# hk310_esc.net
KiCad netlist of a schematic drawn in EAGLE
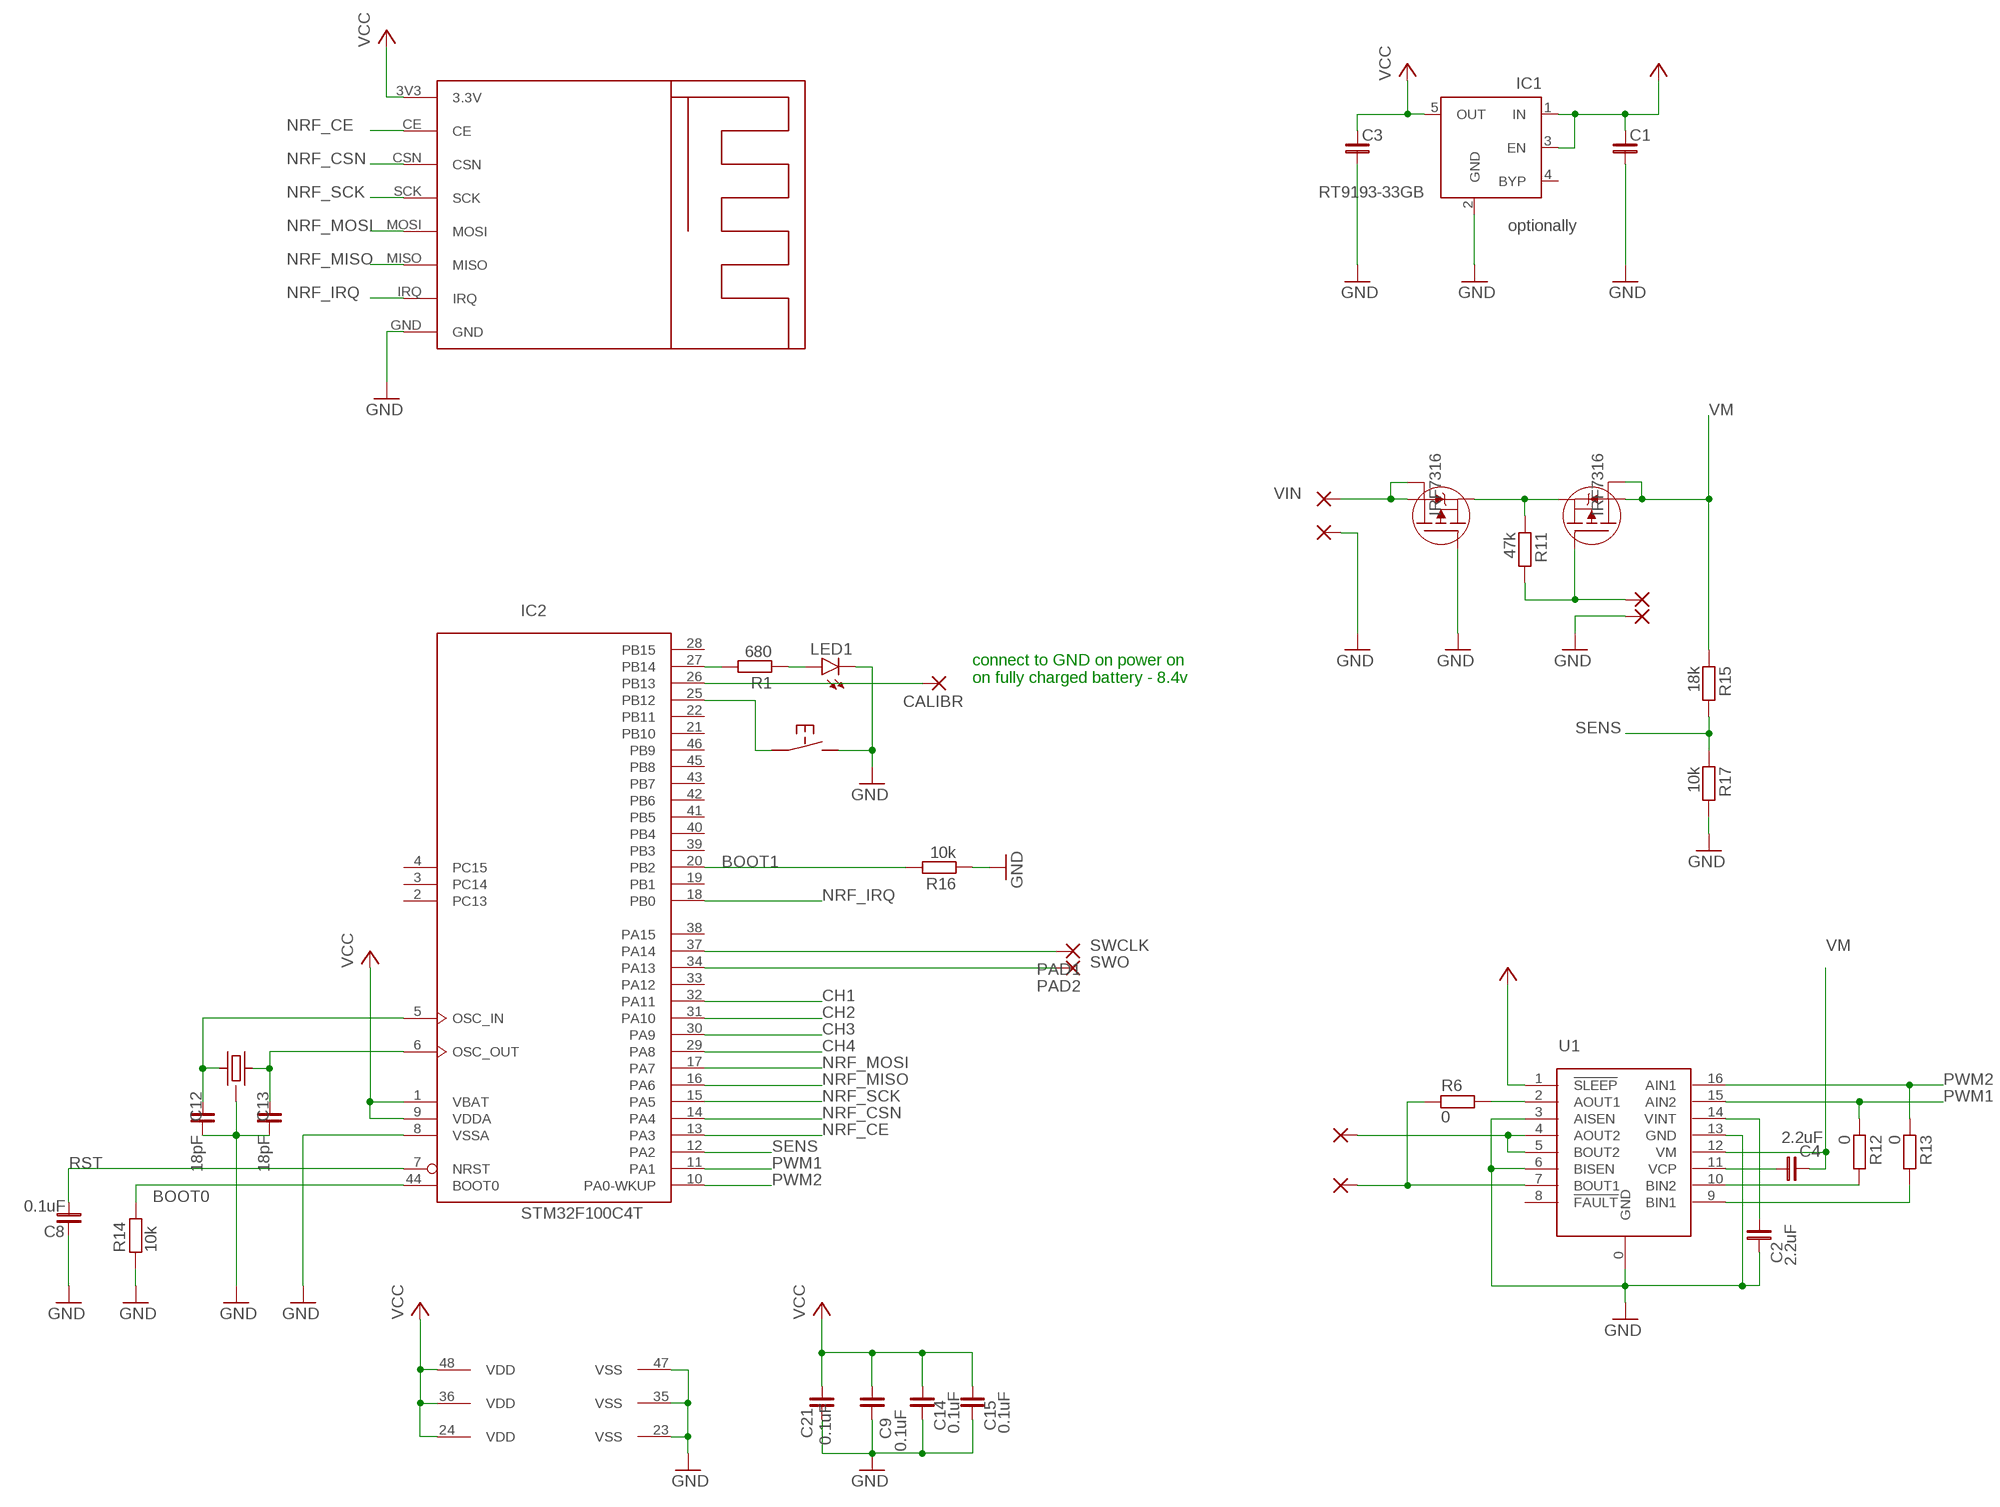
[diagram p0: schematic, sheet 1, part 1 of 2]
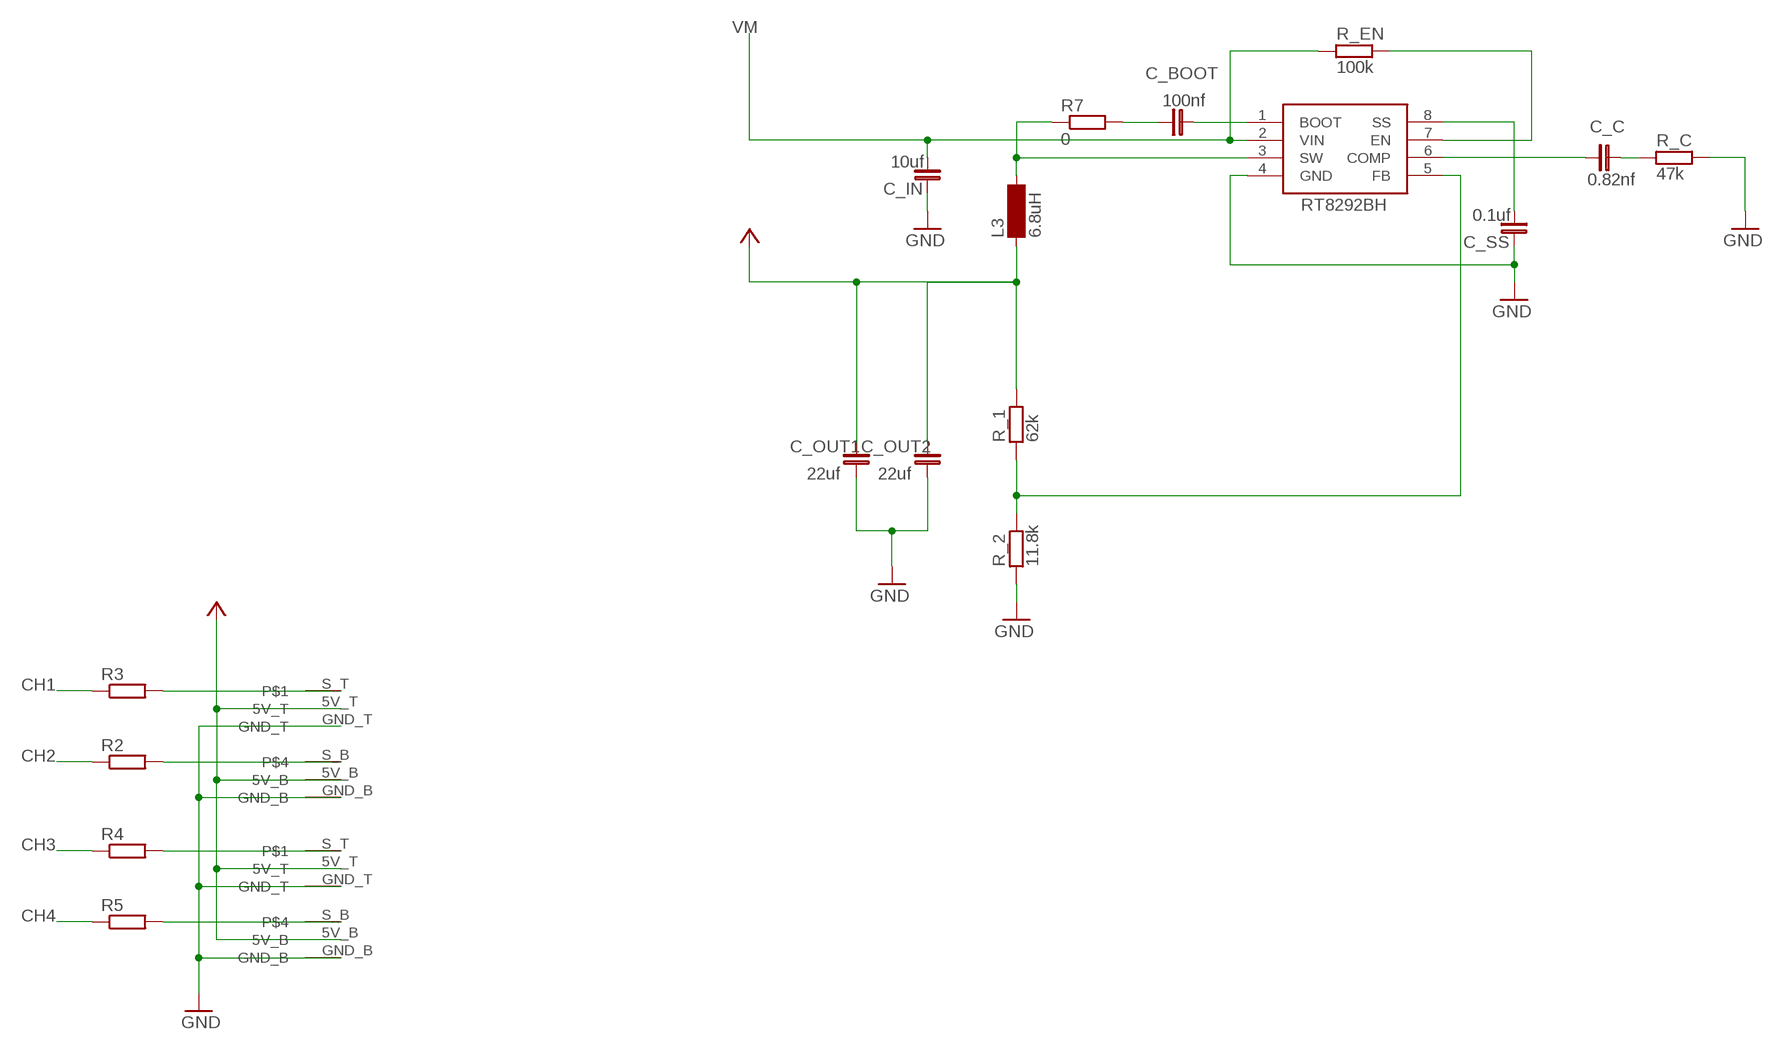
[diagram p1: schematic, sheet 1, part 2 of 2]

(export (version "E")
  (design (tool "Eeschema 10.0.6"))
  (components
    (comp (ref "C1")
      (value "C_0805")
      (footprint "eagle-import:C0805")
      (libsource (lib "eagle-import") (part "C_0805"))
    )
    (comp (ref "C2")
      (value "2.2uF")
      (footprint "eagle-import:C0805")
      (libsource (lib "eagle-import") (part "C_0805"))
    )
    (comp (ref "C3")
      (value "C_0805")
      (footprint "eagle-import:C0805")
      (libsource (lib "eagle-import") (part "C_0805"))
    )
    (comp (ref "C4")
      (value "2.2uF")
      (footprint "eagle-import:C0805")
      (libsource (lib "eagle-import") (part "C_0805"))
    )
    (comp (ref "C8")
      (value "0.1uF")
      (footprint "eagle-import:C0603")
      (libsource (lib "eagle-import") (part "C_0603"))
    )
    (comp (ref "C9")
      (value "0.1uF")
      (footprint "eagle-import:C0603")
      (libsource (lib "eagle-import") (part "C_0603"))
    )
    (comp (ref "C12")
      (value "18pF")
      (footprint "eagle-import:C0603")
      (libsource (lib "eagle-import") (part "C_0603"))
    )
    (comp (ref "C13")
      (value "18pF")
      (footprint "eagle-import:C0603")
      (libsource (lib "eagle-import") (part "C_0603"))
    )
    (comp (ref "C14")
      (value "0.1uF")
      (footprint "eagle-import:C0603")
      (libsource (lib "eagle-import") (part "C_0603"))
    )
    (comp (ref "C15")
      (value "0.1uF")
      (footprint "eagle-import:C0603")
      (libsource (lib "eagle-import") (part "C_0603"))
    )
    (comp (ref "C21")
      (value "0.1uF")
      (footprint "eagle-import:C0603")
      (libsource (lib "eagle-import") (part "C_0603"))
    )
    (comp (ref "CALIBR")
      (value "SMD2")
      (footprint "eagle-import:SMD1,27-2,54")
      (libsource (lib "eagle-import") (part "SMD2"))
    )
    (comp (ref "C_BOOT")
      (value "100nf")
      (footprint "eagle-import:C0402")
      (libsource (lib "eagle-import") (part "C_0402"))
    )
    (comp (ref "C_C")
      (value "0.82nf")
      (footprint "eagle-import:C0402")
      (libsource (lib "eagle-import") (part "C_0402"))
    )
    (comp (ref "C_IN")
      (value "10uf")
      (footprint "eagle-import:C1206")
      (libsource (lib "eagle-import") (part "C_1206"))
    )
    (comp (ref "C_OUT1")
      (value "22uf")
      (footprint "eagle-import:C0805")
      (libsource (lib "eagle-import") (part "C_0805"))
    )
    (comp (ref "C_OUT2")
      (value "22uf")
      (footprint "eagle-import:C0805")
      (libsource (lib "eagle-import") (part "C_0805"))
    )
    (comp (ref "C_SS")
      (value "0.1uf")
      (footprint "eagle-import:C0402")
      (libsource (lib "eagle-import") (part "C_0402"))
    )
    (comp (ref "IC1")
      (value "RT9193-33GB")
      (footprint "eagle-import:SOT23-5")
      (libsource (lib "eagle-import") (part "MIC5219XX"))
    )
    (comp (ref "IC2")
      (value "STM32F100C4T")
      (footprint "eagle-import:LQFP48")
      (libsource (lib "eagle-import") (part "STM32F100CT4"))
    )
    (comp (ref "L3")
      (value "6.8uH")
      (footprint "eagle-import:MS85")
      (libsource (lib "eagle-import") (part "MS85"))
    )
    (comp (ref "LED1")
      (value "LED")
      (footprint "eagle-import:SMARTLED-TTW")
      (libsource (lib "eagle-import") (part "LED"))
    )
    (comp (ref "PAD1")
      (value "SMD2")
      (footprint "eagle-import:SMD1,27-2,54")
      (libsource (lib "eagle-import") (part "SMD2"))
    )
    (comp (ref "PAD2")
      (value "SMD2")
      (footprint "eagle-import:SMD1,27-2,54")
      (libsource (lib "eagle-import") (part "SMD2"))
    )
    (comp (ref "PAD3")
      (value "WIREPADSMD5-1,8")
      (footprint "eagle-import:5-1,8")
      (libsource (lib "eagle-import") (part "WIREPADSMD5-1,8"))
    )
    (comp (ref "PAD4")
      (value "WIREPADSMD5-1,8")
      (footprint "eagle-import:5-1,8")
      (libsource (lib "eagle-import") (part "WIREPADSMD5-1,8"))
    )
    (comp (ref "PAD5")
      (value "WIREPADSMD5-1,8")
      (footprint "eagle-import:5-1,8")
      (libsource (lib "eagle-import") (part "WIREPADSMD5-1,8"))
    )
    (comp (ref "PAD6")
      (value "WIREPADSMD5-1,8")
      (footprint "eagle-import:5-1,8")
      (libsource (lib "eagle-import") (part "WIREPADSMD5-1,8"))
    )
    (comp (ref "PAD7")
      (value "WIREPADSMD5-1,8")
      (footprint "eagle-import:5-1,8")
      (libsource (lib "eagle-import") (part "WIREPADSMD5-1,8"))
    )
    (comp (ref "PAD8")
      (value "WIREPADSMD5-1,8")
      (footprint "eagle-import:5-1,8")
      (libsource (lib "eagle-import") (part "WIREPADSMD5-1,8"))
    )
    (comp (ref "R1")
      (value "680")
      (footprint "eagle-import:R0805")
      (libsource (lib "eagle-import") (part "R_0805"))
    )
    (comp (ref "R2")
      (value "R-EU_R1206")
      (footprint "eagle-import:R1206")
      (libsource (lib "eagle-import") (part "R-EU_R1206"))
    )
    (comp (ref "R3")
      (value "R-EU_R1206")
      (footprint "eagle-import:R1206")
      (libsource (lib "eagle-import") (part "R-EU_R1206"))
    )
    (comp (ref "R4")
      (value "R-EU_R1206")
      (footprint "eagle-import:R1206")
      (libsource (lib "eagle-import") (part "R-EU_R1206"))
    )
    (comp (ref "R5")
      (value "R-EU_R1206")
      (footprint "eagle-import:R1206")
      (libsource (lib "eagle-import") (part "R-EU_R1206"))
    )
    (comp (ref "R6")
      (value "0")
      (footprint "eagle-import:R1206")
      (libsource (lib "eagle-import") (part "R_1206"))
    )
    (comp (ref "R7")
      (value "0")
      (footprint "eagle-import:R1206")
      (libsource (lib "eagle-import") (part "R-EU_R1206"))
    )
    (comp (ref "R11")
      (value "47k")
      (footprint "eagle-import:R0805")
      (libsource (lib "eagle-import") (part "R_0805"))
    )
    (comp (ref "R12")
      (value "0")
      (footprint "eagle-import:R1206")
      (libsource (lib "eagle-import") (part "R_1206"))
    )
    (comp (ref "R13")
      (value "0")
      (footprint "eagle-import:R1206")
      (libsource (lib "eagle-import") (part "R_1206"))
    )
    (comp (ref "R14")
      (value "10k")
      (footprint "eagle-import:R0805")
      (libsource (lib "eagle-import") (part "R_0805"))
    )
    (comp (ref "R15")
      (value "18k")
      (footprint "eagle-import:R0805")
      (libsource (lib "eagle-import") (part "R_0805"))
    )
    (comp (ref "R16")
      (value "10k")
      (footprint "eagle-import:R0805")
      (libsource (lib "eagle-import") (part "R_0805"))
    )
    (comp (ref "R17")
      (value "10k")
      (footprint "eagle-import:R0805")
      (libsource (lib "eagle-import") (part "R_0805"))
    )
    (comp (ref "RT8292BH")
      (value "RT8292B")
      (footprint "eagle-import:SO8-2")
      (libsource (lib "eagle-import") (part "RT8292B"))
    )
    (comp (ref "R_1")
      (value "62k")
      (footprint "eagle-import:R0402")
      (libsource (lib "eagle-import") (part "R_0402"))
    )
    (comp (ref "R_2")
      (value "11.8k")
      (footprint "eagle-import:R0402")
      (libsource (lib "eagle-import") (part "R_0402"))
    )
    (comp (ref "R_C")
      (value "47k")
      (footprint "eagle-import:R0402")
      (libsource (lib "eagle-import") (part "R_0402"))
    )
    (comp (ref "R_EN")
      (value "100k")
      (footprint "eagle-import:R0402")
      (libsource (lib "eagle-import") (part "R_0402"))
    )
    (comp (ref "U$1")
      (value "NRF24MINI")
      (footprint "eagle-import:NRF24MINI")
      (libsource (lib "eagle-import") (part "NRF24MINI"))
    )
    (comp (ref "U$2")
      (value "PINHEAD_SMD")
      (footprint "eagle-import:PINHEAD_SMD")
      (libsource (lib "eagle-import") (part "PINHEAD_SMD"))
    )
    (comp (ref "U$3")
      (value "PINHEAD_SMD")
      (footprint "eagle-import:PINHEAD_SMD")
      (libsource (lib "eagle-import") (part "PINHEAD_SMD"))
    )
    (comp (ref "U$5")
      (value "IRF7104")
      (footprint "eagle-import:SO8-2")
      (libsource (lib "eagle-import") (part "IRF7104"))
    )
    (comp (ref "U$6")
      (value "8Mhz")
      (footprint "eagle-import:CRYSTAL_3PINS")
      (libsource (lib "eagle-import") (part "CRYSTAL_3PINS"))
    )
    (comp (ref "U$7")
      (value "SMALL_BUTTON")
      (footprint "eagle-import:SMALL_BUTTON")
      (libsource (lib "eagle-import") (part "SMALL_BUTTON"))
    )
    (comp (ref "U1")
      (value "DRV8833")
      (footprint "eagle-import:PWP16")
      (libsource (lib "eagle-import") (part "DRV8833"))
    )
  )
  (nets
    (net (code "1") (name "+5V") (class "Default")
      (node (ref "C1") (pin "1") (pinfunction "1_1") (pintype "passive"))
      (node (ref "C_OUT1") (pin "2") (pinfunction "2_2") (pintype "passive"))
      (node (ref "C_OUT2") (pin "2") (pinfunction "2_2") (pintype "passive"))
      (node (ref "IC1") (pin "1") (pinfunction "IN_1") (pintype "input"))
      (node (ref "IC1") (pin "3") (pinfunction "EN_3") (pintype "input"))
      (node (ref "L3") (pin "1") (pinfunction "1_1") (pintype "passive"))
      (node (ref "R_1") (pin "2") (pinfunction "2_2") (pintype "passive"))
      (node (ref "U$2") (pin "5V_B") (pinfunction "5V_B_5V_B") (pintype "bidirectional"))
      (node (ref "U$2") (pin "5V_T") (pinfunction "5V_T_5V_T") (pintype "bidirectional"))
      (node (ref "U$3") (pin "5V_B") (pinfunction "5V_B_5V_B") (pintype "bidirectional"))
      (node (ref "U$3") (pin "5V_T") (pinfunction "5V_T_5V_T") (pintype "bidirectional"))
      (node (ref "U1") (pin "1") (pinfunction "~{SLEEP}_1") (pintype "bidirectional"))
    )
    (net (code "2") (name "/BOOT0") (class "Default")
      (node (ref "IC2") (pin "44") (pinfunction "BOOT0_44") (pintype "input"))
      (node (ref "R14") (pin "2") (pinfunction "2_2") (pintype "passive"))
    )
    (net (code "3") (name "/BOOT1") (class "Default")
      (node (ref "IC2") (pin "20") (pinfunction "PB2_20") (pintype "bidirectional"))
      (node (ref "R16") (pin "2") (pinfunction "2_2") (pintype "passive"))
    )
    (net (code "4") (name "/CH1") (class "Default")
      (node (ref "IC2") (pin "32") (pinfunction "PA11_32") (pintype "bidirectional"))
      (node (ref "R3") (pin "1") (pinfunction "1_1") (pintype "passive"))
    )
    (net (code "5") (name "/CH2") (class "Default")
      (node (ref "IC2") (pin "31") (pinfunction "PA10_31") (pintype "bidirectional"))
      (node (ref "R2") (pin "1") (pinfunction "1_1") (pintype "passive"))
    )
    (net (code "6") (name "/CH3") (class "Default")
      (node (ref "IC2") (pin "30") (pinfunction "PA9_30") (pintype "bidirectional"))
      (node (ref "R4") (pin "1") (pinfunction "1_1") (pintype "passive"))
    )
    (net (code "7") (name "/CH4") (class "Default")
      (node (ref "IC2") (pin "29") (pinfunction "PA8_29") (pintype "bidirectional"))
      (node (ref "R5") (pin "1") (pinfunction "1_1") (pintype "passive"))
    )
    (net (code "8") (name "/NRF_CE") (class "Default")
      (node (ref "IC2") (pin "13") (pinfunction "PA3_13") (pintype "bidirectional"))
      (node (ref "U$1") (pin "CE") (pinfunction "CE_CE") (pintype "bidirectional"))
    )
    (net (code "9") (name "/NRF_CSN") (class "Default")
      (node (ref "IC2") (pin "14") (pinfunction "PA4_14") (pintype "bidirectional"))
      (node (ref "U$1") (pin "CSN") (pinfunction "CSN_CSN") (pintype "bidirectional"))
    )
    (net (code "10") (name "/NRF_IRQ") (class "Default")
      (node (ref "IC2") (pin "18") (pinfunction "PB0_18") (pintype "bidirectional"))
      (node (ref "U$1") (pin "IRQ") (pinfunction "IRQ_IRQ") (pintype "bidirectional"))
    )
    (net (code "11") (name "/NRF_MISO") (class "Default")
      (node (ref "IC2") (pin "16") (pinfunction "PA6_16") (pintype "bidirectional"))
      (node (ref "U$1") (pin "MISO") (pinfunction "MISO_MISO") (pintype "bidirectional"))
    )
    (net (code "12") (name "/NRF_MOSI") (class "Default")
      (node (ref "IC2") (pin "17") (pinfunction "PA7_17") (pintype "bidirectional"))
      (node (ref "U$1") (pin "MOSI") (pinfunction "MOSI_MOSI") (pintype "bidirectional"))
    )
    (net (code "13") (name "/NRF_SCK") (class "Default")
      (node (ref "IC2") (pin "15") (pinfunction "PA5_15") (pintype "bidirectional"))
      (node (ref "U$1") (pin "SCK") (pinfunction "SCK_SCK") (pintype "bidirectional"))
    )
    (net (code "14") (name "/PWM1") (class "Default")
      (node (ref "IC2") (pin "11") (pinfunction "PA1_11") (pintype "bidirectional"))
      (node (ref "R12") (pin "1") (pinfunction "1_1") (pintype "passive"))
      (node (ref "U1") (pin "15") (pinfunction "AIN2_15") (pintype "bidirectional"))
    )
    (net (code "15") (name "/PWM2") (class "Default")
      (node (ref "IC2") (pin "10") (pinfunction "PA0-WKUP_10") (pintype "bidirectional"))
      (node (ref "R13") (pin "1") (pinfunction "1_1") (pintype "passive"))
      (node (ref "U1") (pin "16") (pinfunction "AIN1_16") (pintype "bidirectional"))
    )
    (net (code "16") (name "/RST") (class "Default")
      (node (ref "C8") (pin "2") (pinfunction "2_2") (pintype "passive"))
      (node (ref "IC2") (pin "7") (pinfunction "NRST_7") (pintype "bidirectional"))
    )
    (net (code "17") (name "/SENS") (class "Default")
      (node (ref "IC2") (pin "12") (pinfunction "PA2_12") (pintype "bidirectional"))
      (node (ref "R15") (pin "2") (pinfunction "2_2") (pintype "passive"))
      (node (ref "R17") (pin "1") (pinfunction "1_1") (pintype "passive"))
    )
    (net (code "18") (name "/SWCLK") (class "Default")
      (node (ref "IC2") (pin "37") (pinfunction "PA14_37") (pintype "bidirectional"))
      (node (ref "PAD1") (pin "1") (pinfunction "P_1") (pintype "passive"))
    )
    (net (code "19") (name "/SWO") (class "Default")
      (node (ref "IC2") (pin "34") (pinfunction "PA13_34") (pintype "bidirectional"))
      (node (ref "PAD2") (pin "1") (pinfunction "P_1") (pintype "passive"))
    )
    (net (code "20") (name "/VIN") (class "Default")
      (node (ref "PAD4") (pin "1") (pinfunction "P_1") (pintype "passive"))
      (node (ref "U$5") (pin "5") (pinfunction "D_5") (pintype "bidirectional"))
      (node (ref "U$5") (pin "6") (pinfunction "D_6") (pintype "bidirectional"))
    )
    (net (code "21") (name "/VM") (class "Default")
      (node (ref "C4") (pin "1") (pinfunction "1_1") (pintype "passive"))
      (node (ref "C_IN") (pin "2") (pinfunction "2_2") (pintype "passive"))
      (node (ref "R15") (pin "1") (pinfunction "1_1") (pintype "passive"))
      (node (ref "RT8292BH") (pin "2") (pinfunction "VIN_2") (pintype "bidirectional"))
      (node (ref "R_EN") (pin "1") (pinfunction "1_1") (pintype "passive"))
      (node (ref "U$5") (pin "7") (pinfunction "D_7") (pintype "bidirectional"))
      (node (ref "U$5") (pin "8") (pinfunction "D_8") (pintype "bidirectional"))
      (node (ref "U1") (pin "12") (pinfunction "VM_12") (pintype "bidirectional"))
    )
    (net (code "22") (name "GND") (class "Default")
      (node (ref "C1") (pin "2") (pinfunction "2_2") (pintype "passive"))
      (node (ref "C12") (pin "1") (pinfunction "1_1") (pintype "passive"))
      (node (ref "C13") (pin "1") (pinfunction "1_1") (pintype "passive"))
      (node (ref "C14") (pin "1") (pinfunction "1_1") (pintype "passive"))
      (node (ref "C15") (pin "1") (pinfunction "1_1") (pintype "passive"))
      (node (ref "C2") (pin "1") (pinfunction "1_1") (pintype "passive"))
      (node (ref "C21") (pin "1") (pinfunction "1_1") (pintype "passive"))
      (node (ref "C3") (pin "2") (pinfunction "2_2") (pintype "passive"))
      (node (ref "C8") (pin "1") (pinfunction "1_1") (pintype "passive"))
      (node (ref "C9") (pin "1") (pinfunction "1_1") (pintype "passive"))
      (node (ref "C_IN") (pin "1") (pinfunction "1_1") (pintype "passive"))
      (node (ref "C_OUT1") (pin "1") (pinfunction "1_1") (pintype "passive"))
      (node (ref "C_OUT2") (pin "1") (pinfunction "1_1") (pintype "passive"))
      (node (ref "C_SS") (pin "1") (pinfunction "1_1") (pintype "passive"))
      (node (ref "IC1") (pin "2") (pinfunction "GND_2") (pintype "power_in"))
      (node (ref "IC2") (pin "23") (pinfunction "VSS_23") (pintype "power_in"))
      (node (ref "IC2") (pin "35") (pinfunction "VSS_35") (pintype "power_in"))
      (node (ref "IC2") (pin "47") (pinfunction "VSS_47") (pintype "power_in"))
      (node (ref "IC2") (pin "8") (pinfunction "VSSA_8") (pintype "power_in"))
      (node (ref "LED1") (pin "C@1") (pinfunction "C_C@1") (pintype "passive"))
      (node (ref "PAD5") (pin "1") (pinfunction "P_1") (pintype "passive"))
      (node (ref "PAD8") (pin "1") (pinfunction "P_1") (pintype "passive"))
      (node (ref "R14") (pin "1") (pinfunction "1_1") (pintype "passive"))
      (node (ref "R16") (pin "1") (pinfunction "1_1") (pintype "passive"))
      (node (ref "R17") (pin "2") (pinfunction "2_2") (pintype "passive"))
      (node (ref "RT8292BH") (pin "4") (pinfunction "GND_4") (pintype "bidirectional"))
      (node (ref "R_2") (pin "1") (pinfunction "1_1") (pintype "passive"))
      (node (ref "R_C") (pin "2") (pinfunction "2_2") (pintype "passive"))
      (node (ref "U$1") (pin "GND") (pinfunction "GND_GND") (pintype "bidirectional"))
      (node (ref "U$2") (pin "GND_B") (pinfunction "GND_B_GND_B") (pintype "bidirectional"))
      (node (ref "U$2") (pin "GND_T") (pinfunction "GND_T_GND_T") (pintype "bidirectional"))
      (node (ref "U$3") (pin "GND_B") (pinfunction "GND_B_GND_B") (pintype "bidirectional"))
      (node (ref "U$3") (pin "GND_T") (pinfunction "GND_T_GND_T") (pintype "bidirectional"))
      (node (ref "U$5") (pin "4") (pinfunction "G_4") (pintype "bidirectional"))
      (node (ref "U$6") (pin "GND") (pinfunction "GND_GND") (pintype "bidirectional"))
      (node (ref "U$7") (pin "2_1") (pinfunction "2_2_1") (pintype "bidirectional"))
      (node (ref "U$7") (pin "2_2") (pinfunction "2_2_2") (pintype "bidirectional"))
      (node (ref "U1") (pin "0") (pinfunction "GND_0") (pintype "bidirectional"))
      (node (ref "U1") (pin "13") (pinfunction "GND_13") (pintype "bidirectional"))
      (node (ref "U1") (pin "3") (pinfunction "AISEN_3") (pintype "bidirectional"))
      (node (ref "U1") (pin "6") (pinfunction "BISEN_6") (pintype "bidirectional"))
    )
    (net (code "23") (name "Net-(CALIBR-P)") (class "Default")
      (node (ref "CALIBR") (pin "1") (pinfunction "P_1") (pintype "passive"))
      (node (ref "IC2") (pin "26") (pinfunction "PB13_26") (pintype "bidirectional"))
    )
    (net (code "24") (name "Net-(C_BOOT-Pad1)") (class "Default")
      (node (ref "C_BOOT") (pin "1") (pinfunction "1_1") (pintype "passive"))
      (node (ref "R7") (pin "2") (pinfunction "2_2") (pintype "passive"))
    )
    (net (code "25") (name "Net-(C_C-Pad2)") (class "Default")
      (node (ref "C_C") (pin "2") (pinfunction "2_2") (pintype "passive"))
      (node (ref "R_C") (pin "1") (pinfunction "1_1") (pintype "passive"))
    )
    (net (code "26") (name "Net-(IC2A-OSC_IN)") (class "Default")
      (node (ref "C12") (pin "2") (pinfunction "2_2") (pintype "passive"))
      (node (ref "IC2") (pin "5") (pinfunction "OSC_IN_5") (pintype "bidirectional"))
      (node (ref "U$6") (pin "P$1") (pinfunction "P$1_P$1") (pintype "bidirectional"))
    )
    (net (code "27") (name "Net-(IC2A-OSC_OUT)") (class "Default")
      (node (ref "C13") (pin "2") (pinfunction "2_2") (pintype "passive"))
      (node (ref "IC2") (pin "6") (pinfunction "OSC_OUT_6") (pintype "bidirectional"))
      (node (ref "U$6") (pin "P$2") (pinfunction "P$2_P$2") (pintype "bidirectional"))
    )
    (net (code "28") (name "Net-(IC2A-PB12)") (class "Default")
      (node (ref "IC2") (pin "25") (pinfunction "PB12_25") (pintype "bidirectional"))
      (node (ref "U$7") (pin "1_1") (pinfunction "1_1_1") (pintype "bidirectional"))
      (node (ref "U$7") (pin "1_2") (pinfunction "1_1_2") (pintype "bidirectional"))
    )
    (net (code "29") (name "Net-(IC2A-PB14)") (class "Default")
      (node (ref "IC2") (pin "27") (pinfunction "PB14_27") (pintype "bidirectional"))
      (node (ref "R1") (pin "2") (pinfunction "2_2") (pintype "passive"))
    )
    (net (code "30") (name "Net-(LED1-A)") (class "Default")
      (node (ref "LED1") (pin "A@1") (pinfunction "A_A@1") (pintype "passive"))
      (node (ref "R1") (pin "1") (pinfunction "1_1") (pintype "passive"))
    )
    (net (code "31") (name "Net-(PAD3-P)") (class "Default")
      (node (ref "PAD3") (pin "1") (pinfunction "P_1") (pintype "passive"))
      (node (ref "U1") (pin "4") (pinfunction "AOUT2_4") (pintype "bidirectional"))
      (node (ref "U1") (pin "5") (pinfunction "BOUT2_5") (pintype "bidirectional"))
    )
    (net (code "32") (name "Net-(PAD6-P)") (class "Default")
      (node (ref "PAD6") (pin "1") (pinfunction "P_1") (pintype "passive"))
      (node (ref "R11") (pin "2") (pinfunction "2_2") (pintype "passive"))
      (node (ref "U$5") (pin "2") (pinfunction "G_2") (pintype "bidirectional"))
    )
    (net (code "33") (name "Net-(PAD7-P)") (class "Default")
      (node (ref "PAD7") (pin "1") (pinfunction "P_1") (pintype "passive"))
      (node (ref "R6") (pin "1") (pinfunction "1_1") (pintype "passive"))
      (node (ref "U1") (pin "7") (pinfunction "BOUT1_7") (pintype "bidirectional"))
    )
    (net (code "34") (name "Net-(RT8292BH-BOOT)") (class "Default")
      (node (ref "C_BOOT") (pin "2") (pinfunction "2_2") (pintype "passive"))
      (node (ref "RT8292BH") (pin "1") (pinfunction "BOOT_1") (pintype "bidirectional"))
    )
    (net (code "35") (name "Net-(RT8292BH-COMP)") (class "Default")
      (node (ref "C_C") (pin "1") (pinfunction "1_1") (pintype "passive"))
      (node (ref "RT8292BH") (pin "6") (pinfunction "COMP_6") (pintype "bidirectional"))
    )
    (net (code "36") (name "Net-(RT8292BH-EN)") (class "Default")
      (node (ref "RT8292BH") (pin "7") (pinfunction "EN_7") (pintype "bidirectional"))
      (node (ref "R_EN") (pin "2") (pinfunction "2_2") (pintype "passive"))
    )
    (net (code "37") (name "Net-(RT8292BH-FB)") (class "Default")
      (node (ref "RT8292BH") (pin "5") (pinfunction "FB_5") (pintype "bidirectional"))
      (node (ref "R_1") (pin "1") (pinfunction "1_1") (pintype "passive"))
      (node (ref "R_2") (pin "2") (pinfunction "2_2") (pintype "passive"))
    )
    (net (code "38") (name "Net-(RT8292BH-SS)") (class "Default")
      (node (ref "C_SS") (pin "2") (pinfunction "2_2") (pintype "passive"))
      (node (ref "RT8292BH") (pin "8") (pinfunction "SS_8") (pintype "bidirectional"))
    )
    (net (code "39") (name "Net-(RT8292BH-SW)") (class "Default")
      (node (ref "L3") (pin "2") (pinfunction "2_2") (pintype "passive"))
      (node (ref "R7") (pin "1") (pinfunction "1_1") (pintype "passive"))
      (node (ref "RT8292BH") (pin "3") (pinfunction "SW_3") (pintype "bidirectional"))
    )
    (net (code "40") (name "Net-(U$2-P$1)") (class "Default")
      (node (ref "R3") (pin "2") (pinfunction "2_2") (pintype "passive"))
      (node (ref "U$2") (pin "S_T") (pinfunction "P$1_S_T") (pintype "bidirectional"))
    )
    (net (code "41") (name "Net-(U$2-P$4)") (class "Default")
      (node (ref "R2") (pin "2") (pinfunction "2_2") (pintype "passive"))
      (node (ref "U$2") (pin "S_B") (pinfunction "P$4_S_B") (pintype "bidirectional"))
    )
    (net (code "42") (name "Net-(U$3-P$1)") (class "Default")
      (node (ref "R4") (pin "2") (pinfunction "2_2") (pintype "passive"))
      (node (ref "U$3") (pin "S_T") (pinfunction "P$1_S_T") (pintype "bidirectional"))
    )
    (net (code "43") (name "Net-(U$3-P$4)") (class "Default")
      (node (ref "R5") (pin "2") (pinfunction "2_2") (pintype "passive"))
      (node (ref "U$3") (pin "S_B") (pinfunction "P$4_S_B") (pintype "bidirectional"))
    )
    (net (code "44") (name "Net-(U$5A-S)") (class "Default")
      (node (ref "R11") (pin "1") (pinfunction "1_1") (pintype "passive"))
      (node (ref "U$5") (pin "1") (pinfunction "S_1") (pintype "bidirectional"))
      (node (ref "U$5") (pin "3") (pinfunction "S_3") (pintype "bidirectional"))
    )
    (net (code "45") (name "Net-(U1-AOUT1)") (class "Default")
      (node (ref "R6") (pin "2") (pinfunction "2_2") (pintype "passive"))
      (node (ref "U1") (pin "2") (pinfunction "AOUT1_2") (pintype "bidirectional"))
    )
    (net (code "46") (name "Net-(U1-BIN1)") (class "Default")
      (node (ref "R13") (pin "2") (pinfunction "2_2") (pintype "passive"))
      (node (ref "U1") (pin "9") (pinfunction "BIN1_9") (pintype "bidirectional"))
    )
    (net (code "47") (name "Net-(U1-BIN2)") (class "Default")
      (node (ref "R12") (pin "2") (pinfunction "2_2") (pintype "passive"))
      (node (ref "U1") (pin "10") (pinfunction "BIN2_10") (pintype "bidirectional"))
    )
    (net (code "48") (name "Net-(U1-VCP)") (class "Default")
      (node (ref "C4") (pin "2") (pinfunction "2_2") (pintype "passive"))
      (node (ref "U1") (pin "11") (pinfunction "VCP_11") (pintype "bidirectional"))
    )
    (net (code "49") (name "Net-(U1-VINT)") (class "Default")
      (node (ref "C2") (pin "2") (pinfunction "2_2") (pintype "passive"))
      (node (ref "U1") (pin "14") (pinfunction "VINT_14") (pintype "bidirectional"))
    )
    (net (code "50") (name "VCC") (class "Default")
      (node (ref "C14") (pin "2") (pinfunction "2_2") (pintype "passive"))
      (node (ref "C15") (pin "2") (pinfunction "2_2") (pintype "passive"))
      (node (ref "C21") (pin "2") (pinfunction "2_2") (pintype "passive"))
      (node (ref "C3") (pin "1") (pinfunction "1_1") (pintype "passive"))
      (node (ref "C9") (pin "2") (pinfunction "2_2") (pintype "passive"))
      (node (ref "IC1") (pin "5") (pinfunction "OUT_5") (pintype "output"))
      (node (ref "IC2") (pin "1") (pinfunction "VBAT_1") (pintype "power_in"))
      (node (ref "IC2") (pin "24") (pinfunction "VDD_24") (pintype "power_in"))
      (node (ref "IC2") (pin "36") (pinfunction "VDD_36") (pintype "power_in"))
      (node (ref "IC2") (pin "48") (pinfunction "VDD_48") (pintype "power_in"))
      (node (ref "IC2") (pin "9") (pinfunction "VDDA_9") (pintype "power_in"))
      (node (ref "U$1") (pin "3V3") (pinfunction "3.3V_3V3") (pintype "bidirectional"))
    )
    (net (code "51") (name "unconnected-(IC1-BYP-Pad4)") (class "Default")
      (node (ref "IC1") (pin "4") (pinfunction "BYP_4") (pintype "passive"))
    )
    (net (code "52") (name "unconnected-(IC2A-PA12-Pad33)") (class "Default")
      (node (ref "IC2") (pin "33") (pinfunction "PA12_33") (pintype "bidirectional"))
    )
    (net (code "53") (name "unconnected-(IC2A-PA15-Pad38)") (class "Default")
      (node (ref "IC2") (pin "38") (pinfunction "PA15_38") (pintype "bidirectional"))
    )
    (net (code "54") (name "unconnected-(IC2A-PB1-Pad19)") (class "Default")
      (node (ref "IC2") (pin "19") (pinfunction "PB1_19") (pintype "bidirectional"))
    )
    (net (code "55") (name "unconnected-(IC2A-PB3-Pad39)") (class "Default")
      (node (ref "IC2") (pin "39") (pinfunction "PB3_39") (pintype "bidirectional"))
    )
    (net (code "56") (name "unconnected-(IC2A-PB4-Pad40)") (class "Default")
      (node (ref "IC2") (pin "40") (pinfunction "PB4_40") (pintype "bidirectional"))
    )
    (net (code "57") (name "unconnected-(IC2A-PB5-Pad41)") (class "Default")
      (node (ref "IC2") (pin "41") (pinfunction "PB5_41") (pintype "bidirectional"))
    )
    (net (code "58") (name "unconnected-(IC2A-PB6-Pad42)") (class "Default")
      (node (ref "IC2") (pin "42") (pinfunction "PB6_42") (pintype "bidirectional"))
    )
    (net (code "59") (name "unconnected-(IC2A-PB7-Pad43)") (class "Default")
      (node (ref "IC2") (pin "43") (pinfunction "PB7_43") (pintype "bidirectional"))
    )
    (net (code "60") (name "unconnected-(IC2A-PB8-Pad45)") (class "Default")
      (node (ref "IC2") (pin "45") (pinfunction "PB8_45") (pintype "bidirectional"))
    )
    (net (code "61") (name "unconnected-(IC2A-PB9-Pad46)") (class "Default")
      (node (ref "IC2") (pin "46") (pinfunction "PB9_46") (pintype "bidirectional"))
    )
    (net (code "62") (name "unconnected-(IC2A-PB10-Pad21)") (class "Default")
      (node (ref "IC2") (pin "21") (pinfunction "PB10_21") (pintype "bidirectional"))
    )
    (net (code "63") (name "unconnected-(IC2A-PB11-Pad22)") (class "Default")
      (node (ref "IC2") (pin "22") (pinfunction "PB11_22") (pintype "bidirectional"))
    )
    (net (code "64") (name "unconnected-(IC2A-PB15-Pad28)") (class "Default")
      (node (ref "IC2") (pin "28") (pinfunction "PB15_28") (pintype "bidirectional"))
    )
    (net (code "65") (name "unconnected-(IC2A-PC13-Pad2)") (class "Default")
      (node (ref "IC2") (pin "2") (pinfunction "PC13_2") (pintype "bidirectional"))
    )
    (net (code "66") (name "unconnected-(IC2A-PC14-Pad3)") (class "Default")
      (node (ref "IC2") (pin "3") (pinfunction "PC14_3") (pintype "bidirectional"))
    )
    (net (code "67") (name "unconnected-(IC2A-PC15-Pad4)") (class "Default")
      (node (ref "IC2") (pin "4") (pinfunction "PC15_4") (pintype "bidirectional"))
    )
    (net (code "68") (name "unconnected-(U1-~{FAULT}-Pad8)") (class "Default")
      (node (ref "U1") (pin "8") (pinfunction "~{FAULT}_8") (pintype "bidirectional"))
    )
  )
)
